# Sheet1.net
KiCad netlist of a schematic drawn in Altium Designer
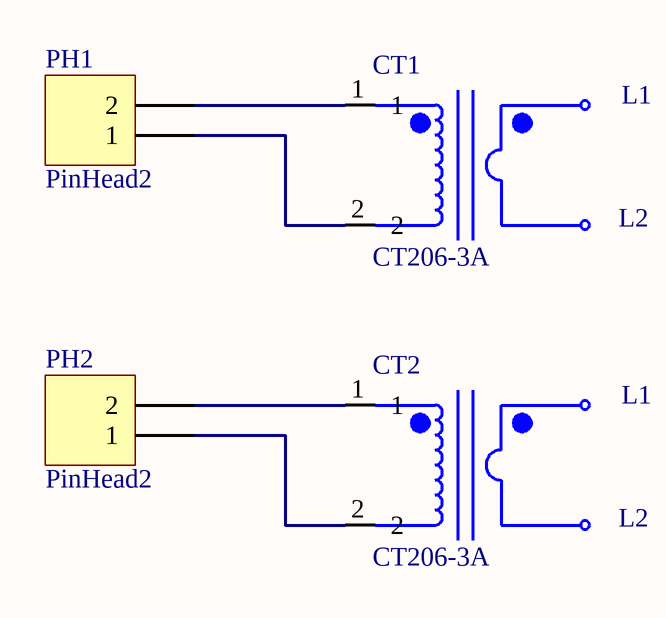
[diagram p0: Sheet1.SchDoc]

(export (version "E")
  (design (tool "Eeschema 10.0.6"))
  (components
    (comp (ref "CT1")
      (value "CT206-3A")
      (footprint "CT206-3A")
      (description "PTH Current Transformer")
      (libsource (lib "SPaivachlib1") (part "CT206-3A"))
    )
    (comp (ref "CT2")
      (value "CT206-3A")
      (footprint "CT206-3A")
      (description "PTH Current Transformer")
      (libsource (lib "SPaivachlib1") (part "CT206-3A"))
    )
    (comp (ref "PH1")
      (value "PinHead2")
      (footprint "PinHead2")
      (libsource (lib "SPaivachlib1") (part "PinHead2"))
    )
    (comp (ref "PH2")
      (value "PinHead2")
      (footprint "PinHead2")
      (libsource (lib "SPaivachlib1") (part "PinHead2"))
    )
  )
  (nets
    (net (code "1") (name "Net-(CT1-Pad1)") (class "Default")
      (node (ref "CT1") (pin "1") (pinfunction "1_1") (pintype "passive"))
      (node (ref "PH1") (pin "2") (pinfunction "2_2") (pintype "passive"))
    )
    (net (code "2") (name "Net-(CT1-Pad2)") (class "Default")
      (node (ref "CT1") (pin "2") (pinfunction "2_2") (pintype "passive"))
      (node (ref "PH1") (pin "1") (pinfunction "1_1") (pintype "passive"))
    )
    (net (code "3") (name "Net-(CT2-Pad1)") (class "Default")
      (node (ref "CT2") (pin "1") (pinfunction "1_1") (pintype "passive"))
      (node (ref "PH2") (pin "2") (pinfunction "2_2") (pintype "passive"))
    )
    (net (code "4") (name "Net-(CT2-Pad2)") (class "Default")
      (node (ref "CT2") (pin "2") (pinfunction "2_2") (pintype "passive"))
      (node (ref "PH2") (pin "1") (pinfunction "1_1") (pintype "passive"))
    )
  )
)
